# DivisorPotResistva.net
KiCad netlist of a schematic drawn in Altium Designer
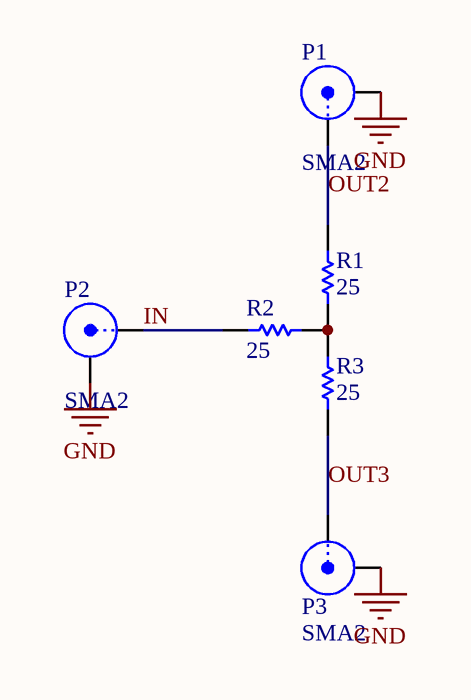
[diagram p0: DivisorPotResistva.SchDoc]

(export (version "E")
  (design (tool "Eeschema 10.0.6"))
  (components
    (comp (ref "P1")
      (value "SMA2")
      (footprint "SMAL2")
      (description "BNC Elbow Connector")
      (fields (field (name "PUBLISHER") "Altium Limited"))
      (libsource (lib "epf") (part "SMA2"))
    )
    (comp (ref "P2")
      (value "SMA2")
      (footprint "SMAL2")
      (description "BNC Elbow Connector")
      (fields (field (name "PUBLISHER") "Altium Limited"))
      (libsource (lib "epf") (part "SMA2"))
    )
    (comp (ref "P3")
      (value "SMA2")
      (footprint "SMAL2")
      (description "BNC Elbow Connector")
      (fields (field (name "PUBLISHER") "Altium Limited"))
      (libsource (lib "epf") (part "SMA2"))
    )
    (comp (ref "R1")
      (value "25")
      (footprint "0805_RES")
      (fields (field (name "Comment") "Resistor"))
      (libsource (lib "epf") (part "Res"))
    )
    (comp (ref "R2")
      (value "25")
      (footprint "0805_RES")
      (fields (field (name "Comment") "Resistor"))
      (libsource (lib "epf") (part "Res"))
    )
    (comp (ref "R3")
      (value "25")
      (footprint "0805_RES")
      (fields (field (name "Comment") "Resistor"))
      (libsource (lib "epf") (part "Res"))
    )
  )
  (nets
    (net (code "1") (name "/IN") (class "Default")
      (node (ref "P2") (pin "1") (pinfunction "X_1") (pintype "passive"))
      (node (ref "R2") (pin "1") (pinfunction "1_1") (pintype "passive"))
    )
    (net (code "2") (name "/OUT2") (class "Default")
      (node (ref "P1") (pin "1") (pinfunction "X_1") (pintype "passive"))
      (node (ref "R1") (pin "2") (pinfunction "2_2") (pintype "passive"))
    )
    (net (code "3") (name "/OUT3") (class "Default")
      (node (ref "P3") (pin "1") (pinfunction "X_1") (pintype "passive"))
      (node (ref "R3") (pin "1") (pinfunction "1_1") (pintype "passive"))
    )
    (net (code "4") (name "GND") (class "Default")
      (node (ref "P1") (pin "0") (pinfunction "Y_0") (pintype "passive"))
      (node (ref "P2") (pin "0") (pinfunction "Y_0") (pintype "passive"))
      (node (ref "P3") (pin "0") (pinfunction "Y_0") (pintype "passive"))
    )
    (net (code "5") (name "Net-(R1-Pad1)") (class "Default")
      (node (ref "R1") (pin "1") (pinfunction "1_1") (pintype "passive"))
      (node (ref "R2") (pin "2") (pinfunction "2_2") (pintype "passive"))
      (node (ref "R3") (pin "2") (pinfunction "2_2") (pintype "passive"))
    )
  )
)
